# dual_sensor.net
KiCad netlist of a schematic drawn in EAGLE
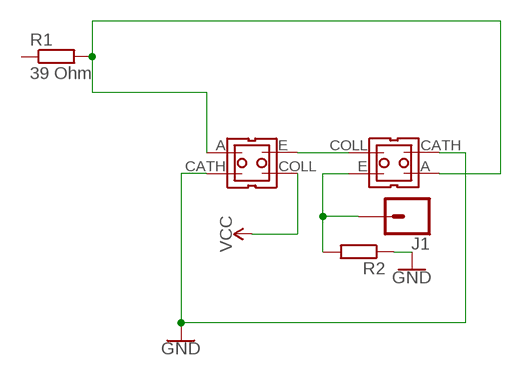
[diagram p0: schematic, sheet 1]

(export (version "E")
  (design (tool "Eeschema 10.0.6"))
  (components
    (comp (ref "J1")
      (value "CONN_01")
      (footprint "eagle-import:1X01")
      (libsource (lib "eagle-import") (part "CONN_01"))
    )
    (comp (ref "R1")
      (value "39 Ohm")
      (footprint "eagle-import:0204_5")
      (libsource (lib "eagle-import") (part "R-EU_0204/5"))
    )
    (comp (ref "R2")
      (value "R-EU_0204/5")
      (footprint "eagle-import:0204_5")
      (libsource (lib "eagle-import") (part "R-EU_0204/5"))
    )
    (comp (ref "U$1")
      (value "CNY70")
      (footprint "eagle-import:CNY70")
      (libsource (lib "eagle-import") (part "CNY70"))
    )
    (comp (ref "U$2")
      (value "CNY70")
      (footprint "eagle-import:CNY70")
      (libsource (lib "eagle-import") (part "CNY70"))
    )
  )
  (nets
    (net (code "1") (name "GND") (class "Default")
      (node (ref "R2") (pin "1") (pinfunction "1_1") (pintype "passive"))
      (node (ref "U$1") (pin "CATH") (pinfunction "GND(DIG)_CATH") (pintype "power_in"))
      (node (ref "U$2") (pin "CATH") (pinfunction "GND(DIG)_CATH") (pintype "power_in"))
    )
    (net (code "2") (name "Net-(U$1-5V(DIG))") (class "Default")
      (node (ref "R1") (pin "2") (pinfunction "2_2") (pintype "passive"))
      (node (ref "U$1") (pin "A") (pinfunction "5V(DIG)_A") (pintype "power_in"))
      (node (ref "U$2") (pin "A") (pinfunction "5V(DIG)_A") (pintype "power_in"))
    )
    (net (code "3") (name "Net-(U$1-GND(PWR))") (class "Default")
      (node (ref "U$1") (pin "E") (pinfunction "GND(PWR)_E") (pintype "power_in"))
      (node (ref "U$2") (pin "COLL") (pinfunction "5V(PWR)_COLL") (pintype "power_in"))
    )
    (net (code "4") (name "Net-(U$2-GND(PWR))") (class "Default")
      (node (ref "J1") (pin "1") (pinfunction "1_1") (pintype "passive"))
      (node (ref "R2") (pin "2") (pinfunction "2_2") (pintype "passive"))
      (node (ref "U$2") (pin "E") (pinfunction "GND(PWR)_E") (pintype "power_in"))
    )
    (net (code "5") (name "VCC") (class "Default")
      (node (ref "U$1") (pin "COLL") (pinfunction "5V(PWR)_COLL") (pintype "power_in"))
    )
    (net (code "6") (name "unconnected-(R1-Pad1)") (class "Default")
      (node (ref "R1") (pin "1") (pinfunction "1_1") (pintype "passive"))
    )
  )
)
